# Thunderbread.net
KiCad netlist of a schematic drawn in EAGLE
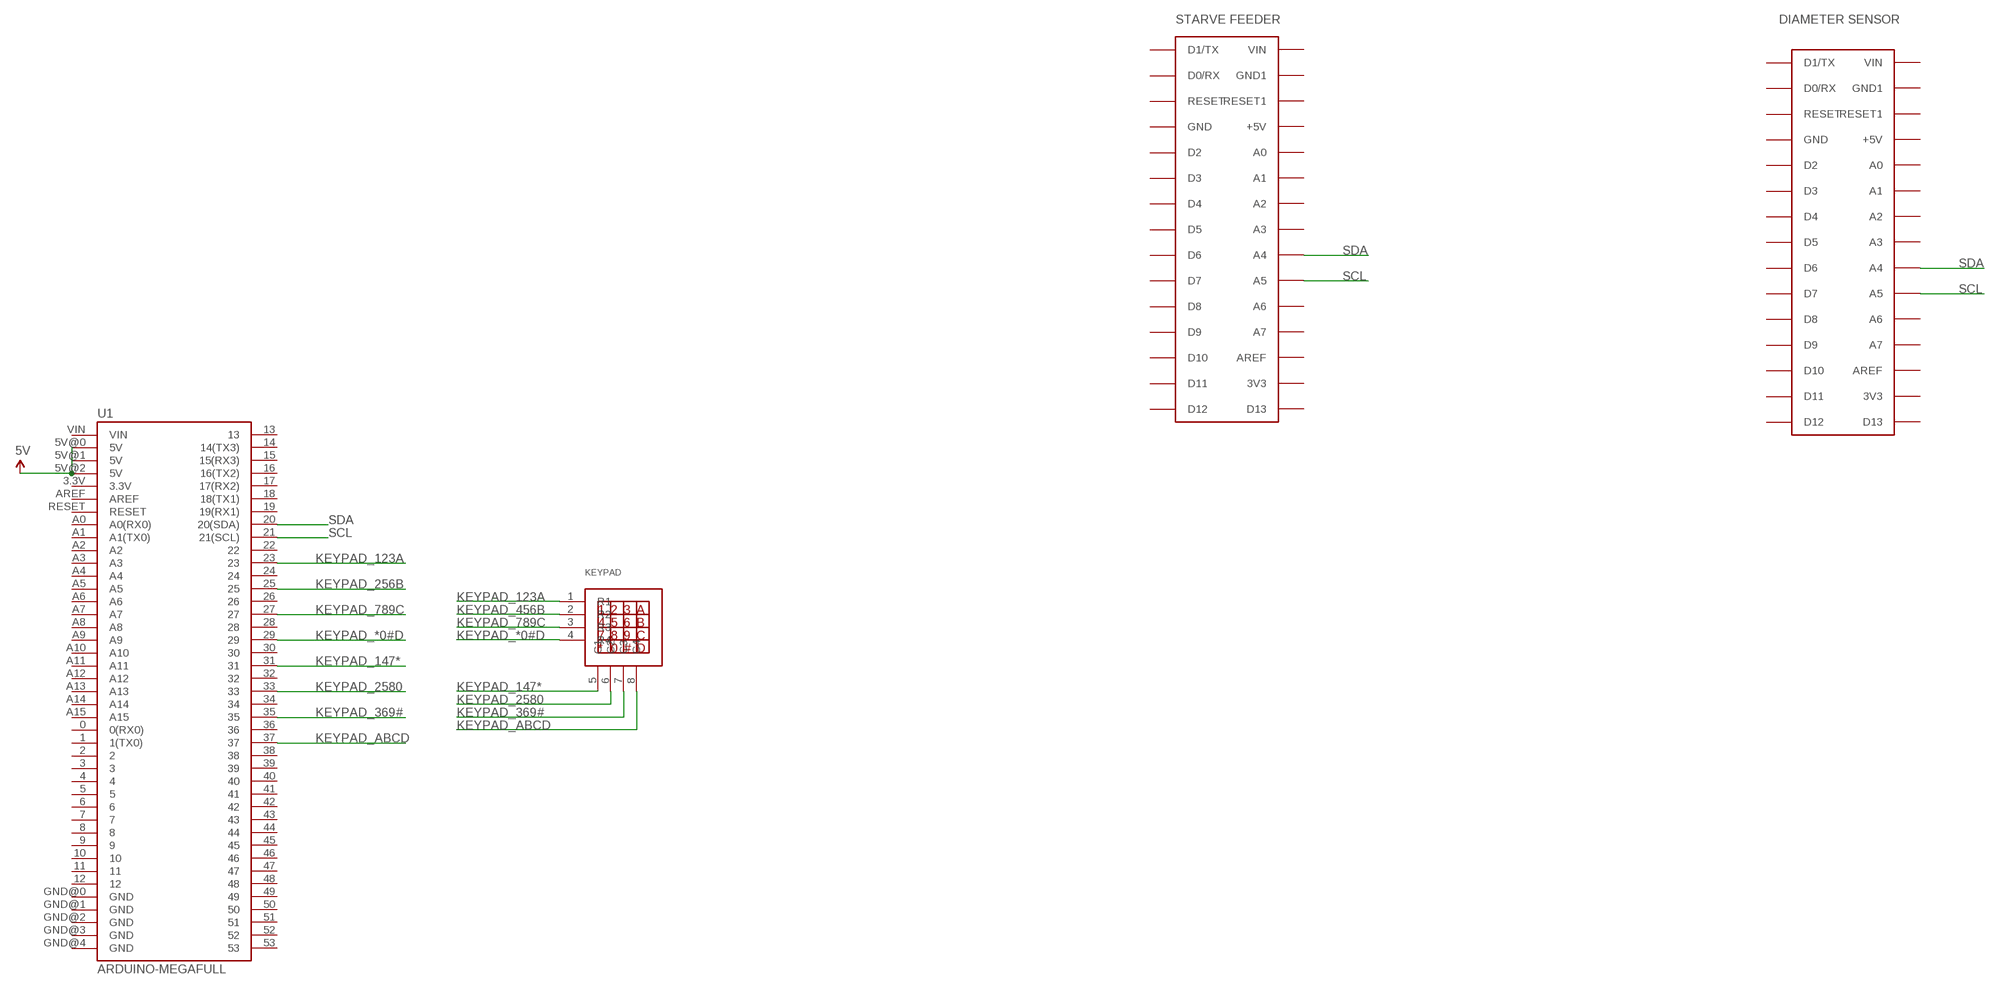
[diagram p0: schematic, sheet 1]

(export (version "E")
  (design (tool "Eeschema 10.0.6"))
  (components
    (comp (ref "KEYPAD")
      (value "KEYPAD4X4")
      (footprint "eagle-import:KEYPAD4X4")
      (libsource (lib "eagle-import") (part "KEYPAD4X4"))
    )
    (comp (ref "U$1")
      (value "ARDUINONANO")
      (footprint "eagle-import:PDIP-32")
      (libsource (lib "eagle-import") (part "ARDUINONANO"))
    )
    (comp (ref "U$2")
      (value "ARDUINONANO")
      (footprint "eagle-import:PDIP-32")
      (libsource (lib "eagle-import") (part "ARDUINONANO"))
    )
    (comp (ref "U1")
      (value "ARDUINO-MEGAFULL")
      (footprint "eagle-import:ARDUINO_MEGA")
      (libsource (lib "eagle-import") (part "ARDUINO-MEGAFULL"))
    )
  )
  (nets
    (net (code "1") (name "/KEYPAD_*0#D") (class "Default")
      (node (ref "KEYPAD") (pin "4") (pinfunction "R4_4") (pintype "bidirectional"))
      (node (ref "U1") (pin "29") (pinfunction "29_29") (pintype "bidirectional"))
    )
    (net (code "2") (name "/KEYPAD_123A") (class "Default")
      (node (ref "KEYPAD") (pin "1") (pinfunction "R1_1") (pintype "bidirectional"))
      (node (ref "U1") (pin "23") (pinfunction "23_23") (pintype "bidirectional"))
    )
    (net (code "3") (name "/KEYPAD_147*") (class "Default")
      (node (ref "KEYPAD") (pin "5") (pinfunction "C1_5") (pintype "bidirectional"))
      (node (ref "U1") (pin "31") (pinfunction "31_31") (pintype "bidirectional"))
    )
    (net (code "4") (name "/KEYPAD_256B") (class "Default")
      (node (ref "U1") (pin "25") (pinfunction "25_25") (pintype "bidirectional"))
    )
    (net (code "5") (name "/KEYPAD_369#") (class "Default")
      (node (ref "KEYPAD") (pin "7") (pinfunction "C3_7") (pintype "bidirectional"))
      (node (ref "U1") (pin "35") (pinfunction "35_35") (pintype "bidirectional"))
    )
    (net (code "6") (name "/KEYPAD_456B") (class "Default")
      (node (ref "KEYPAD") (pin "2") (pinfunction "R2_2") (pintype "bidirectional"))
    )
    (net (code "7") (name "/KEYPAD_789C") (class "Default")
      (node (ref "KEYPAD") (pin "3") (pinfunction "R3_3") (pintype "bidirectional"))
      (node (ref "U1") (pin "27") (pinfunction "27_27") (pintype "bidirectional"))
    )
    (net (code "8") (name "/KEYPAD_2580") (class "Default")
      (node (ref "KEYPAD") (pin "6") (pinfunction "C2_6") (pintype "bidirectional"))
      (node (ref "U1") (pin "33") (pinfunction "33_33") (pintype "bidirectional"))
    )
    (net (code "9") (name "/KEYPAD_ABCD") (class "Default")
      (node (ref "KEYPAD") (pin "8") (pinfunction "C4_8") (pintype "bidirectional"))
      (node (ref "U1") (pin "37") (pinfunction "37_37") (pintype "bidirectional"))
    )
    (net (code "10") (name "/SCL") (class "Default")
      (node (ref "U$1") (pin "A5") (pinfunction "A5_A5") (pintype "bidirectional"))
      (node (ref "U$2") (pin "A5") (pinfunction "A5_A5") (pintype "bidirectional"))
      (node (ref "U1") (pin "21") (pinfunction "21(SCL)_21") (pintype "bidirectional"))
    )
    (net (code "11") (name "/SDA") (class "Default")
      (node (ref "U$1") (pin "A4") (pinfunction "A4_A4") (pintype "bidirectional"))
      (node (ref "U$2") (pin "A4") (pinfunction "A4_A4") (pintype "bidirectional"))
      (node (ref "U1") (pin "20") (pinfunction "20(SDA)_20") (pintype "bidirectional"))
    )
    (net (code "12") (name "5V") (class "Default")
      (node (ref "U1") (pin "5V@0") (pinfunction "5V_5V@0") (pintype "bidirectional"))
      (node (ref "U1") (pin "5V@2") (pinfunction "5V_5V@2") (pintype "bidirectional"))
    )
    (net (code "13") (name "unconnected-(U$1-Pad+5V)") (class "Default")
      (node (ref "U$1") (pin "+5V") (pinfunction "+5V_+5V") (pintype "bidirectional"))
    )
    (net (code "14") (name "unconnected-(U$1-Pad3V3)") (class "Default")
      (node (ref "U$1") (pin "3V3") (pinfunction "3V3_3V3") (pintype "bidirectional"))
    )
    (net (code "15") (name "unconnected-(U$1-PadA0)") (class "Default")
      (node (ref "U$1") (pin "A0") (pinfunction "A0_A0") (pintype "bidirectional"))
    )
    (net (code "16") (name "unconnected-(U$1-PadA1)") (class "Default")
      (node (ref "U$1") (pin "A1") (pinfunction "A1_A1") (pintype "bidirectional"))
    )
    (net (code "17") (name "unconnected-(U$1-PadA2)") (class "Default")
      (node (ref "U$1") (pin "A2") (pinfunction "A2_A2") (pintype "bidirectional"))
    )
    (net (code "18") (name "unconnected-(U$1-PadA3)") (class "Default")
      (node (ref "U$1") (pin "A3") (pinfunction "A3_A3") (pintype "bidirectional"))
    )
    (net (code "19") (name "unconnected-(U$1-PadA6)") (class "Default")
      (node (ref "U$1") (pin "A6") (pinfunction "A6_A6") (pintype "bidirectional"))
    )
    (net (code "20") (name "unconnected-(U$1-PadA7)") (class "Default")
      (node (ref "U$1") (pin "A7") (pinfunction "A7_A7") (pintype "bidirectional"))
    )
    (net (code "21") (name "unconnected-(U$1-PadAREF)") (class "Default")
      (node (ref "U$1") (pin "AREF") (pinfunction "AREF_AREF") (pintype "bidirectional"))
    )
    (net (code "22") (name "unconnected-(U$1-PadD0{slash}RX)") (class "Default")
      (node (ref "U$1") (pin "D0/RX") (pinfunction "D0/RX_D0/RX") (pintype "bidirectional"))
    )
    (net (code "23") (name "unconnected-(U$1-PadD1{slash}TX)") (class "Default")
      (node (ref "U$1") (pin "D1/TX") (pinfunction "D1/TX_D1/TX") (pintype "bidirectional"))
    )
    (net (code "24") (name "unconnected-(U$1-PadD2)") (class "Default")
      (node (ref "U$1") (pin "D2") (pinfunction "D2_D2") (pintype "bidirectional"))
    )
    (net (code "25") (name "unconnected-(U$1-PadD3)") (class "Default")
      (node (ref "U$1") (pin "D3") (pinfunction "D3_D3") (pintype "bidirectional"))
    )
    (net (code "26") (name "unconnected-(U$1-PadD4)") (class "Default")
      (node (ref "U$1") (pin "D4") (pinfunction "D4_D4") (pintype "bidirectional"))
    )
    (net (code "27") (name "unconnected-(U$1-PadD5)") (class "Default")
      (node (ref "U$1") (pin "D5") (pinfunction "D5_D5") (pintype "bidirectional"))
    )
    (net (code "28") (name "unconnected-(U$1-PadD6)") (class "Default")
      (node (ref "U$1") (pin "D6") (pinfunction "D6_D6") (pintype "bidirectional"))
    )
    (net (code "29") (name "unconnected-(U$1-PadD7)") (class "Default")
      (node (ref "U$1") (pin "D7") (pinfunction "D7_D7") (pintype "bidirectional"))
    )
    (net (code "30") (name "unconnected-(U$1-PadD8)") (class "Default")
      (node (ref "U$1") (pin "D8") (pinfunction "D8_D8") (pintype "bidirectional"))
    )
    (net (code "31") (name "unconnected-(U$1-PadD9)") (class "Default")
      (node (ref "U$1") (pin "D9") (pinfunction "D9_D9") (pintype "bidirectional"))
    )
    (net (code "32") (name "unconnected-(U$1-PadD10)") (class "Default")
      (node (ref "U$1") (pin "D10") (pinfunction "D10_D10") (pintype "bidirectional"))
    )
    (net (code "33") (name "unconnected-(U$1-PadD11)") (class "Default")
      (node (ref "U$1") (pin "D11") (pinfunction "D11_D11") (pintype "bidirectional"))
    )
    (net (code "34") (name "unconnected-(U$1-PadD12)") (class "Default")
      (node (ref "U$1") (pin "D12") (pinfunction "D12_D12") (pintype "bidirectional"))
    )
    (net (code "35") (name "unconnected-(U$1-PadD13)") (class "Default")
      (node (ref "U$1") (pin "D13") (pinfunction "D13_D13") (pintype "bidirectional"))
    )
    (net (code "36") (name "unconnected-(U$1-PadGND)") (class "Default")
      (node (ref "U$1") (pin "GND") (pinfunction "GND_GND") (pintype "bidirectional"))
    )
    (net (code "37") (name "unconnected-(U$1-PadGND1)") (class "Default")
      (node (ref "U$1") (pin "GND1") (pinfunction "GND1_GND1") (pintype "bidirectional"))
    )
    (net (code "38") (name "unconnected-(U$1-PadRESET)") (class "Default")
      (node (ref "U$1") (pin "RESET") (pinfunction "RESET_RESET") (pintype "bidirectional"))
    )
    (net (code "39") (name "unconnected-(U$1-PadRESET1)") (class "Default")
      (node (ref "U$1") (pin "RESET1") (pinfunction "RESET1_RESET1") (pintype "bidirectional"))
    )
    (net (code "40") (name "unconnected-(U$1-PadVIN)") (class "Default")
      (node (ref "U$1") (pin "VIN") (pinfunction "VIN_VIN") (pintype "bidirectional"))
    )
    (net (code "41") (name "unconnected-(U$2-Pad+5V)") (class "Default")
      (node (ref "U$2") (pin "+5V") (pinfunction "+5V_+5V") (pintype "bidirectional"))
    )
    (net (code "42") (name "unconnected-(U$2-Pad3V3)") (class "Default")
      (node (ref "U$2") (pin "3V3") (pinfunction "3V3_3V3") (pintype "bidirectional"))
    )
    (net (code "43") (name "unconnected-(U$2-PadA0)") (class "Default")
      (node (ref "U$2") (pin "A0") (pinfunction "A0_A0") (pintype "bidirectional"))
    )
    (net (code "44") (name "unconnected-(U$2-PadA1)") (class "Default")
      (node (ref "U$2") (pin "A1") (pinfunction "A1_A1") (pintype "bidirectional"))
    )
    (net (code "45") (name "unconnected-(U$2-PadA2)") (class "Default")
      (node (ref "U$2") (pin "A2") (pinfunction "A2_A2") (pintype "bidirectional"))
    )
    (net (code "46") (name "unconnected-(U$2-PadA3)") (class "Default")
      (node (ref "U$2") (pin "A3") (pinfunction "A3_A3") (pintype "bidirectional"))
    )
    (net (code "47") (name "unconnected-(U$2-PadA6)") (class "Default")
      (node (ref "U$2") (pin "A6") (pinfunction "A6_A6") (pintype "bidirectional"))
    )
    (net (code "48") (name "unconnected-(U$2-PadA7)") (class "Default")
      (node (ref "U$2") (pin "A7") (pinfunction "A7_A7") (pintype "bidirectional"))
    )
    (net (code "49") (name "unconnected-(U$2-PadAREF)") (class "Default")
      (node (ref "U$2") (pin "AREF") (pinfunction "AREF_AREF") (pintype "bidirectional"))
    )
    (net (code "50") (name "unconnected-(U$2-PadD0{slash}RX)") (class "Default")
      (node (ref "U$2") (pin "D0/RX") (pinfunction "D0/RX_D0/RX") (pintype "bidirectional"))
    )
    (net (code "51") (name "unconnected-(U$2-PadD1{slash}TX)") (class "Default")
      (node (ref "U$2") (pin "D1/TX") (pinfunction "D1/TX_D1/TX") (pintype "bidirectional"))
    )
    (net (code "52") (name "unconnected-(U$2-PadD2)") (class "Default")
      (node (ref "U$2") (pin "D2") (pinfunction "D2_D2") (pintype "bidirectional"))
    )
    (net (code "53") (name "unconnected-(U$2-PadD3)") (class "Default")
      (node (ref "U$2") (pin "D3") (pinfunction "D3_D3") (pintype "bidirectional"))
    )
    (net (code "54") (name "unconnected-(U$2-PadD4)") (class "Default")
      (node (ref "U$2") (pin "D4") (pinfunction "D4_D4") (pintype "bidirectional"))
    )
    (net (code "55") (name "unconnected-(U$2-PadD5)") (class "Default")
      (node (ref "U$2") (pin "D5") (pinfunction "D5_D5") (pintype "bidirectional"))
    )
    (net (code "56") (name "unconnected-(U$2-PadD6)") (class "Default")
      (node (ref "U$2") (pin "D6") (pinfunction "D6_D6") (pintype "bidirectional"))
    )
    (net (code "57") (name "unconnected-(U$2-PadD7)") (class "Default")
      (node (ref "U$2") (pin "D7") (pinfunction "D7_D7") (pintype "bidirectional"))
    )
    (net (code "58") (name "unconnected-(U$2-PadD8)") (class "Default")
      (node (ref "U$2") (pin "D8") (pinfunction "D8_D8") (pintype "bidirectional"))
    )
    (net (code "59") (name "unconnected-(U$2-PadD9)") (class "Default")
      (node (ref "U$2") (pin "D9") (pinfunction "D9_D9") (pintype "bidirectional"))
    )
    (net (code "60") (name "unconnected-(U$2-PadD10)") (class "Default")
      (node (ref "U$2") (pin "D10") (pinfunction "D10_D10") (pintype "bidirectional"))
    )
    (net (code "61") (name "unconnected-(U$2-PadD11)") (class "Default")
      (node (ref "U$2") (pin "D11") (pinfunction "D11_D11") (pintype "bidirectional"))
    )
    (net (code "62") (name "unconnected-(U$2-PadD12)") (class "Default")
      (node (ref "U$2") (pin "D12") (pinfunction "D12_D12") (pintype "bidirectional"))
    )
    (net (code "63") (name "unconnected-(U$2-PadD13)") (class "Default")
      (node (ref "U$2") (pin "D13") (pinfunction "D13_D13") (pintype "bidirectional"))
    )
    (net (code "64") (name "unconnected-(U$2-PadGND)") (class "Default")
      (node (ref "U$2") (pin "GND") (pinfunction "GND_GND") (pintype "bidirectional"))
    )
    (net (code "65") (name "unconnected-(U$2-PadGND1)") (class "Default")
      (node (ref "U$2") (pin "GND1") (pinfunction "GND1_GND1") (pintype "bidirectional"))
    )
    (net (code "66") (name "unconnected-(U$2-PadRESET)") (class "Default")
      (node (ref "U$2") (pin "RESET") (pinfunction "RESET_RESET") (pintype "bidirectional"))
    )
    (net (code "67") (name "unconnected-(U$2-PadRESET1)") (class "Default")
      (node (ref "U$2") (pin "RESET1") (pinfunction "RESET1_RESET1") (pintype "bidirectional"))
    )
    (net (code "68") (name "unconnected-(U$2-PadVIN)") (class "Default")
      (node (ref "U$2") (pin "VIN") (pinfunction "VIN_VIN") (pintype "bidirectional"))
    )
    (net (code "69") (name "unconnected-(U1-0(RX0)-Pad0)") (class "Default")
      (node (ref "U1") (pin "0") (pinfunction "0(RX0)_0") (pintype "bidirectional"))
    )
    (net (code "70") (name "unconnected-(U1-1(TX0)-Pad1)") (class "Default")
      (node (ref "U1") (pin "1") (pinfunction "1(TX0)_1") (pintype "bidirectional"))
    )
    (net (code "71") (name "unconnected-(U1-5V-Pad5V@1)") (class "Default")
      (node (ref "U1") (pin "5V@1") (pinfunction "5V_5V@1") (pintype "bidirectional"))
    )
    (net (code "72") (name "unconnected-(U1-14(TX3)-Pad14)") (class "Default")
      (node (ref "U1") (pin "14") (pinfunction "14(TX3)_14") (pintype "bidirectional"))
    )
    (net (code "73") (name "unconnected-(U1-15(RX3)-Pad15)") (class "Default")
      (node (ref "U1") (pin "15") (pinfunction "15(RX3)_15") (pintype "bidirectional"))
    )
    (net (code "74") (name "unconnected-(U1-16(TX2)-Pad16)") (class "Default")
      (node (ref "U1") (pin "16") (pinfunction "16(TX2)_16") (pintype "bidirectional"))
    )
    (net (code "75") (name "unconnected-(U1-17(RX2)-Pad17)") (class "Default")
      (node (ref "U1") (pin "17") (pinfunction "17(RX2)_17") (pintype "bidirectional"))
    )
    (net (code "76") (name "unconnected-(U1-18(TX1)-Pad18)") (class "Default")
      (node (ref "U1") (pin "18") (pinfunction "18(TX1)_18") (pintype "bidirectional"))
    )
    (net (code "77") (name "unconnected-(U1-19(RX1)-Pad19)") (class "Default")
      (node (ref "U1") (pin "19") (pinfunction "19(RX1)_19") (pintype "bidirectional"))
    )
    (net (code "78") (name "unconnected-(U1-A0(RX0)-PadA0)") (class "Default")
      (node (ref "U1") (pin "A0") (pinfunction "A0(RX0)_A0") (pintype "bidirectional"))
    )
    (net (code "79") (name "unconnected-(U1-A1(TX0)-PadA1)") (class "Default")
      (node (ref "U1") (pin "A1") (pinfunction "A1(TX0)_A1") (pintype "bidirectional"))
    )
    (net (code "80") (name "unconnected-(U1-GND-PadGND@0)") (class "Default")
      (node (ref "U1") (pin "GND@0") (pinfunction "GND_GND@0") (pintype "bidirectional"))
    )
    (net (code "81") (name "unconnected-(U1-GND-PadGND@1)") (class "Default")
      (node (ref "U1") (pin "GND@1") (pinfunction "GND_GND@1") (pintype "bidirectional"))
    )
    (net (code "82") (name "unconnected-(U1-GND-PadGND@2)") (class "Default")
      (node (ref "U1") (pin "GND@2") (pinfunction "GND_GND@2") (pintype "bidirectional"))
    )
    (net (code "83") (name "unconnected-(U1-GND-PadGND@3)") (class "Default")
      (node (ref "U1") (pin "GND@3") (pinfunction "GND_GND@3") (pintype "bidirectional"))
    )
    (net (code "84") (name "unconnected-(U1-GND-PadGND@4)") (class "Default")
      (node (ref "U1") (pin "GND@4") (pinfunction "GND_GND@4") (pintype "bidirectional"))
    )
    (net (code "85") (name "unconnected-(U1-Pad2)") (class "Default")
      (node (ref "U1") (pin "2") (pinfunction "2_2") (pintype "bidirectional"))
    )
    (net (code "86") (name "unconnected-(U1-Pad3)") (class "Default")
      (node (ref "U1") (pin "3") (pinfunction "3_3") (pintype "bidirectional"))
    )
    (net (code "87") (name "unconnected-(U1-Pad3.3V)") (class "Default")
      (node (ref "U1") (pin "3.3V") (pinfunction "3.3V_3.3V") (pintype "bidirectional"))
    )
    (net (code "88") (name "unconnected-(U1-Pad4)") (class "Default")
      (node (ref "U1") (pin "4") (pinfunction "4_4") (pintype "bidirectional"))
    )
    (net (code "89") (name "unconnected-(U1-Pad5)") (class "Default")
      (node (ref "U1") (pin "5") (pinfunction "5_5") (pintype "bidirectional"))
    )
    (net (code "90") (name "unconnected-(U1-Pad6)") (class "Default")
      (node (ref "U1") (pin "6") (pinfunction "6_6") (pintype "bidirectional"))
    )
    (net (code "91") (name "unconnected-(U1-Pad7)") (class "Default")
      (node (ref "U1") (pin "7") (pinfunction "7_7") (pintype "bidirectional"))
    )
    (net (code "92") (name "unconnected-(U1-Pad8)") (class "Default")
      (node (ref "U1") (pin "8") (pinfunction "8_8") (pintype "bidirectional"))
    )
    (net (code "93") (name "unconnected-(U1-Pad9)") (class "Default")
      (node (ref "U1") (pin "9") (pinfunction "9_9") (pintype "bidirectional"))
    )
    (net (code "94") (name "unconnected-(U1-Pad10)") (class "Default")
      (node (ref "U1") (pin "10") (pinfunction "10_10") (pintype "bidirectional"))
    )
    (net (code "95") (name "unconnected-(U1-Pad11)") (class "Default")
      (node (ref "U1") (pin "11") (pinfunction "11_11") (pintype "bidirectional"))
    )
    (net (code "96") (name "unconnected-(U1-Pad12)") (class "Default")
      (node (ref "U1") (pin "12") (pinfunction "12_12") (pintype "bidirectional"))
    )
    (net (code "97") (name "unconnected-(U1-Pad13)") (class "Default")
      (node (ref "U1") (pin "13") (pinfunction "13_13") (pintype "bidirectional"))
    )
    (net (code "98") (name "unconnected-(U1-Pad22)") (class "Default")
      (node (ref "U1") (pin "22") (pinfunction "22_22") (pintype "bidirectional"))
    )
    (net (code "99") (name "unconnected-(U1-Pad24)") (class "Default")
      (node (ref "U1") (pin "24") (pinfunction "24_24") (pintype "bidirectional"))
    )
    (net (code "100") (name "unconnected-(U1-Pad26)") (class "Default")
      (node (ref "U1") (pin "26") (pinfunction "26_26") (pintype "bidirectional"))
    )
    (net (code "101") (name "unconnected-(U1-Pad28)") (class "Default")
      (node (ref "U1") (pin "28") (pinfunction "28_28") (pintype "bidirectional"))
    )
    (net (code "102") (name "unconnected-(U1-Pad30)") (class "Default")
      (node (ref "U1") (pin "30") (pinfunction "30_30") (pintype "bidirectional"))
    )
    (net (code "103") (name "unconnected-(U1-Pad32)") (class "Default")
      (node (ref "U1") (pin "32") (pinfunction "32_32") (pintype "bidirectional"))
    )
    (net (code "104") (name "unconnected-(U1-Pad34)") (class "Default")
      (node (ref "U1") (pin "34") (pinfunction "34_34") (pintype "bidirectional"))
    )
    (net (code "105") (name "unconnected-(U1-Pad36)") (class "Default")
      (node (ref "U1") (pin "36") (pinfunction "36_36") (pintype "bidirectional"))
    )
    (net (code "106") (name "unconnected-(U1-Pad38)") (class "Default")
      (node (ref "U1") (pin "38") (pinfunction "38_38") (pintype "bidirectional"))
    )
    (net (code "107") (name "unconnected-(U1-Pad39)") (class "Default")
      (node (ref "U1") (pin "39") (pinfunction "39_39") (pintype "bidirectional"))
    )
    (net (code "108") (name "unconnected-(U1-Pad40)") (class "Default")
      (node (ref "U1") (pin "40") (pinfunction "40_40") (pintype "bidirectional"))
    )
    (net (code "109") (name "unconnected-(U1-Pad41)") (class "Default")
      (node (ref "U1") (pin "41") (pinfunction "41_41") (pintype "bidirectional"))
    )
    (net (code "110") (name "unconnected-(U1-Pad42)") (class "Default")
      (node (ref "U1") (pin "42") (pinfunction "42_42") (pintype "bidirectional"))
    )
    (net (code "111") (name "unconnected-(U1-Pad43)") (class "Default")
      (node (ref "U1") (pin "43") (pinfunction "43_43") (pintype "bidirectional"))
    )
    (net (code "112") (name "unconnected-(U1-Pad44)") (class "Default")
      (node (ref "U1") (pin "44") (pinfunction "44_44") (pintype "bidirectional"))
    )
    (net (code "113") (name "unconnected-(U1-Pad45)") (class "Default")
      (node (ref "U1") (pin "45") (pinfunction "45_45") (pintype "bidirectional"))
    )
    (net (code "114") (name "unconnected-(U1-Pad46)") (class "Default")
      (node (ref "U1") (pin "46") (pinfunction "46_46") (pintype "bidirectional"))
    )
    (net (code "115") (name "unconnected-(U1-Pad47)") (class "Default")
      (node (ref "U1") (pin "47") (pinfunction "47_47") (pintype "bidirectional"))
    )
    (net (code "116") (name "unconnected-(U1-Pad48)") (class "Default")
      (node (ref "U1") (pin "48") (pinfunction "48_48") (pintype "bidirectional"))
    )
    (net (code "117") (name "unconnected-(U1-Pad49)") (class "Default")
      (node (ref "U1") (pin "49") (pinfunction "49_49") (pintype "bidirectional"))
    )
    (net (code "118") (name "unconnected-(U1-Pad50)") (class "Default")
      (node (ref "U1") (pin "50") (pinfunction "50_50") (pintype "bidirectional"))
    )
    (net (code "119") (name "unconnected-(U1-Pad51)") (class "Default")
      (node (ref "U1") (pin "51") (pinfunction "51_51") (pintype "bidirectional"))
    )
    (net (code "120") (name "unconnected-(U1-Pad52)") (class "Default")
      (node (ref "U1") (pin "52") (pinfunction "52_52") (pintype "bidirectional"))
    )
    (net (code "121") (name "unconnected-(U1-Pad53)") (class "Default")
      (node (ref "U1") (pin "53") (pinfunction "53_53") (pintype "bidirectional"))
    )
    (net (code "122") (name "unconnected-(U1-PadA2)") (class "Default")
      (node (ref "U1") (pin "A2") (pinfunction "A2_A2") (pintype "bidirectional"))
    )
    (net (code "123") (name "unconnected-(U1-PadA3)") (class "Default")
      (node (ref "U1") (pin "A3") (pinfunction "A3_A3") (pintype "bidirectional"))
    )
    (net (code "124") (name "unconnected-(U1-PadA4)") (class "Default")
      (node (ref "U1") (pin "A4") (pinfunction "A4_A4") (pintype "bidirectional"))
    )
    (net (code "125") (name "unconnected-(U1-PadA5)") (class "Default")
      (node (ref "U1") (pin "A5") (pinfunction "A5_A5") (pintype "bidirectional"))
    )
    (net (code "126") (name "unconnected-(U1-PadA6)") (class "Default")
      (node (ref "U1") (pin "A6") (pinfunction "A6_A6") (pintype "bidirectional"))
    )
    (net (code "127") (name "unconnected-(U1-PadA7)") (class "Default")
      (node (ref "U1") (pin "A7") (pinfunction "A7_A7") (pintype "bidirectional"))
    )
    (net (code "128") (name "unconnected-(U1-PadA8)") (class "Default")
      (node (ref "U1") (pin "A8") (pinfunction "A8_A8") (pintype "bidirectional"))
    )
    (net (code "129") (name "unconnected-(U1-PadA9)") (class "Default")
      (node (ref "U1") (pin "A9") (pinfunction "A9_A9") (pintype "bidirectional"))
    )
    (net (code "130") (name "unconnected-(U1-PadA10)") (class "Default")
      (node (ref "U1") (pin "A10") (pinfunction "A10_A10") (pintype "bidirectional"))
    )
    (net (code "131") (name "unconnected-(U1-PadA11)") (class "Default")
      (node (ref "U1") (pin "A11") (pinfunction "A11_A11") (pintype "bidirectional"))
    )
    (net (code "132") (name "unconnected-(U1-PadA12)") (class "Default")
      (node (ref "U1") (pin "A12") (pinfunction "A12_A12") (pintype "bidirectional"))
    )
    (net (code "133") (name "unconnected-(U1-PadA13)") (class "Default")
      (node (ref "U1") (pin "A13") (pinfunction "A13_A13") (pintype "bidirectional"))
    )
    (net (code "134") (name "unconnected-(U1-PadA14)") (class "Default")
      (node (ref "U1") (pin "A14") (pinfunction "A14_A14") (pintype "bidirectional"))
    )
    (net (code "135") (name "unconnected-(U1-PadA15)") (class "Default")
      (node (ref "U1") (pin "A15") (pinfunction "A15_A15") (pintype "bidirectional"))
    )
    (net (code "136") (name "unconnected-(U1-PadAREF)") (class "Default")
      (node (ref "U1") (pin "AREF") (pinfunction "AREF_AREF") (pintype "bidirectional"))
    )
    (net (code "137") (name "unconnected-(U1-PadRESET)") (class "Default")
      (node (ref "U1") (pin "RESET") (pinfunction "RESET_RESET") (pintype "bidirectional"))
    )
    (net (code "138") (name "unconnected-(U1-PadVIN)") (class "Default")
      (node (ref "U1") (pin "VIN") (pinfunction "VIN_VIN") (pintype "bidirectional"))
    )
  )
)
